# cuk.net
KiCad netlist of a schematic drawn in Altium Designer
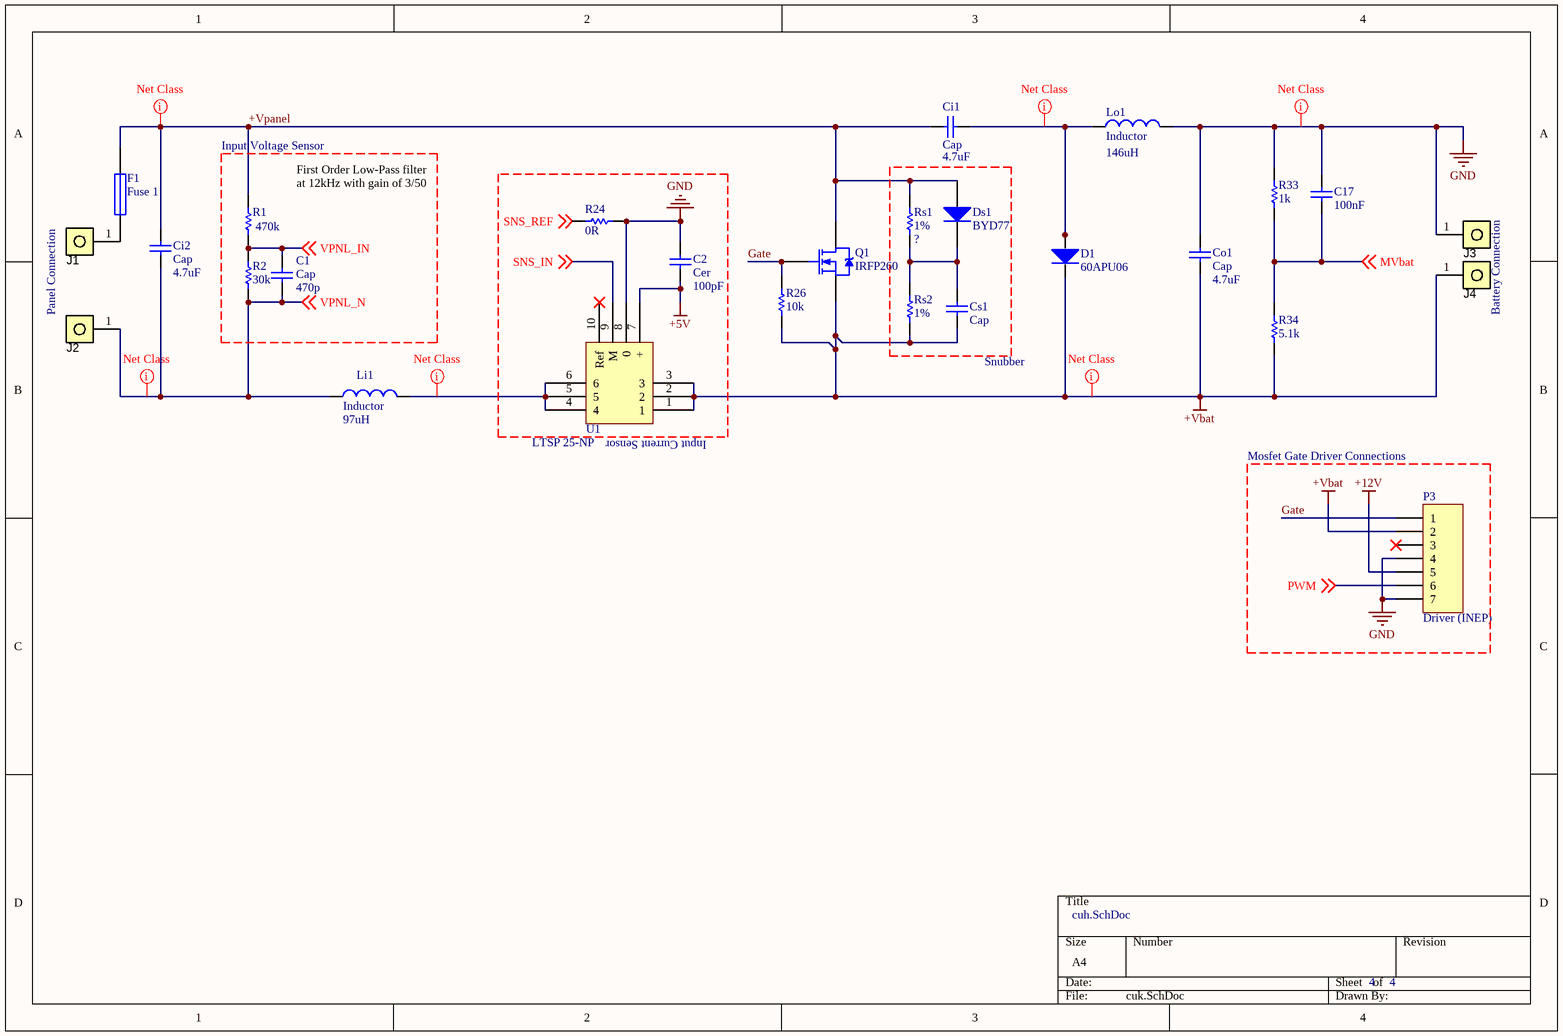
[diagram p0: cuk.SchDoc]

(export (version "E")
  (design (tool "Eeschema 10.0.6"))
  (components
    (comp (ref "C1")
      (value "Cap")
      (footprint "6-0805_N")
      (description "Capacitor")
      (fields (field (name "ALTIUM_VALUE") "470p") (field (name "PUBLISHER") "Altium Limited"))
      (libsource (lib "Miscellaneous Devices") (part "Cap"))
    )
    (comp (ref "C2")
      (value "Cer")
      (footprint "C1210_M")
      (description "Capacitor")
      (fields (field (name "ALTIUM_VALUE") "100pF") (field (name "PUBLISHER") "Altium Limited"))
      (libsource (lib "Miscellaneous Devices") (part "Cap"))
    )
    (comp (ref "C17")
      (value "100nF")
      (footprint "6-0805_M")
      (description "Capacitor")
      (fields (field (name "PUBLISHER") "Altium Limited"))
      (libsource (lib "ControladorCarga") (part "Cap_3"))
    )
    (comp (ref "Ci1")
      (value "Cap")
      (footprint "CAP4U7 EPCOS")
      (description "Capacitor")
      (fields (field (name "ALTIUM_VALUE") "4.7uF") (field (name "PUBLISHER") "Altium Limited"))
      (libsource (lib "Miscellaneous Devices") (part "Cap"))
    )
    (comp (ref "Ci2")
      (value "Cap")
      (footprint "CAP4U7 EPCOS")
      (description "Capacitor")
      (fields (field (name "ALTIUM_VALUE") "4.7uF") (field (name "PUBLISHER") "Altium Limited"))
      (libsource (lib "Miscellaneous Devices") (part "Cap"))
    )
    (comp (ref "Co1")
      (value "Cap")
      (footprint "CAP4U7 EPCOS")
      (description "Capacitor")
      (fields (field (name "ALTIUM_VALUE") "4.7uF") (field (name "PUBLISHER") "Altium Limited"))
      (libsource (lib "Miscellaneous Devices") (part "Cap"))
    )
    (comp (ref "Cs1")
      (value "Cap")
      (footprint "100nF")
      (description "Capacitor")
      (fields (field (name "PUBLISHER") "Altium Limited"))
      (libsource (lib "Miscellaneous Devices") (part "Cap"))
    )
    (comp (ref "D1")
      (value "60APU06")
      (footprint "to-247ac_horizontal")
      (libsource (lib "Prototipo") (part "60APU06"))
    )
    (comp (ref "Ds1")
      (value "BYD77")
      (footprint "SOD87")
      (description "1 Amp General Purpose Rectifier")
      (fields (field (name "PUBLISHER") "Altium Limited"))
      (libsource (lib "Miscellaneous Devices") (part "Diode 1N4002"))
    )
    (comp (ref "F1")
      (value "Fuse 1")
      (footprint "FUSE HOLDER 5X20")
      (description "Fuse")
      (fields (field (name "PUBLISHER") "Altium Limited"))
      (libsource (lib "TRACTEBEL") (part "Fuse 1"))
    )
    (comp (ref "J1") (value "~") (footprint "Parafuso") (libsource (lib "") (part "CONN_1_BIG_1")))
    (comp (ref "J2") (value "~") (footprint "Parafuso") (libsource (lib "") (part "CONN_1_BIG_1")))
    (comp (ref "J3")
      (value "~")
      (footprint "Parafuso")
      (libsource (lib "DatabaseAltium") (part "CONN_1_BIG"))
    )
    (comp (ref "J4")
      (value "~")
      (footprint "Parafuso")
      (libsource (lib "DatabaseAltium") (part "CONN_1_BIG"))
    )
    (comp (ref "Li1")
      (value "Inductor")
      (footprint "NEE-42-20-deitado")
      (fields (field (name "ALTIUM_VALUE") "97uH") (field (name "PUBLISHER") "Altium Limited"))
      (libsource (lib "Miscellaneous Devices") (part "Inductor"))
    )
    (comp (ref "Lo1")
      (value "Inductor")
      (footprint "NEE-42-20-deitado")
      (fields (field (name "ALTIUM_VALUE") "146uH") (field (name "PUBLISHER") "Altium Limited"))
      (libsource (lib "Miscellaneous Devices") (part "Inductor"))
    )
    (comp (ref "P3")
      (value "Driver (INEP)")
      (footprint "Driver INEP")
      (description "Header, 7-Pin")
      (fields (field (name "PUBLISHER") "Altium Limited"))
      (libsource (lib "Miscellaneous Connectors") (part "Header 7"))
    )
    (comp (ref "Q1")
      (value "IRFP260")
      (footprint "to-247ac_horizontal")
      (description "HEXFET Power MOSFET")
      (fields (field (name "PUBLISHER") "Altium Limited"))
      (libsource (lib "IR Discrete MOSFET - Power") (part "IRFP260"))
    )
    (comp (ref "R1")
      (value "470k")
      (footprint "6-0805_N")
      (description "Resistor")
      (fields (field (name "Comment") "Res1") (field (name "PUBLISHER") "Altium Limited"))
      (libsource (lib "Miscellaneous Devices") (part "Res1"))
    )
    (comp (ref "R2")
      (value "30k")
      (footprint "6-0805_N")
      (description "Resistor")
      (fields (field (name "Comment") "Res1") (field (name "PUBLISHER") "Altium Limited"))
      (libsource (lib "Miscellaneous Devices") (part "Res1"))
    )
    (comp (ref "R24")
      (value "0R")
      (footprint "6-0805_N")
      (description "Resistor")
      (fields (field (name "Comment") "Res1") (field (name "PUBLISHER") "Altium Limited"))
      (libsource (lib "Miscellaneous Devices") (part "Res1"))
    )
    (comp (ref "R26")
      (value "10k")
      (footprint "6-0805_N")
      (description "Resistor")
      (fields (field (name "Comment") "Res1") (field (name "PUBLISHER") "Altium Limited"))
      (libsource (lib "Miscellaneous Devices") (part "Res1"))
    )
    (comp (ref "R33")
      (value "1k")
      (footprint "6-0805_M")
      (description "Resistor")
      (fields (field (name "PUBLISHER") "Altium Limited"))
      (libsource (lib "ControladorCarga") (part "Res1"))
    )
    (comp (ref "R34")
      (value "5.1k")
      (footprint "6-0805_M")
      (description "Resistor")
      (fields (field (name "PUBLISHER") "Altium Limited"))
      (libsource (lib "ControladorCarga") (part "Res1"))
    )
    (comp (ref "Rs1")
      (value "1%")
      (footprint "AXIAL-0.3")
      (description "Resistor")
      (fields (field (name "ALTIUM_VALUE") "?") (field (name "PUBLISHER") "Altium Limited"))
      (libsource (lib "Miscellaneous Devices") (part "Res1"))
    )
    (comp (ref "Rs2")
      (value "1%")
      (footprint "AXIAL-0.3")
      (description "Resistor")
      (fields (field (name "PUBLISHER") "Altium Limited"))
      (libsource (lib "Miscellaneous Devices") (part "Res1"))
    )
    (comp (ref "U1")
      (value "LTSP 25-NP")
      (footprint "LTSP 25-NP")
      (description "Current Transducer LTSP (25 A)")
      (libsource (lib "LEM") (part "LTSP 25-NP"))
    )
  )
  (nets
    (net (code "1") (name "+5V") (class "Default")
      (node (ref "C2") (pin "1") (pinfunction "1_1") (pintype "passive"))
      (node (ref "U1") (pin "7") (pinfunction "+_7") (pintype "passive"))
    )
    (net (code "2") (name "+12V") (class "Default")
      (node (ref "P3") (pin "5") (pinfunction "5_5") (pintype "passive"))
    )
    (net (code "3") (name "+Vbat") (class "Default")
      (node (ref "Co1") (pin "1") (pinfunction "1_1") (pintype "passive"))
      (node (ref "Cs1") (pin "1") (pinfunction "1_1") (pintype "passive"))
      (node (ref "D1") (pin "2") (pinfunction "K_2") (pintype "passive"))
      (node (ref "J4") (pin "1") (pinfunction "1_1") (pintype "passive"))
      (node (ref "P3") (pin "2") (pinfunction "2_2") (pintype "passive"))
      (node (ref "Q1") (pin "3") (pinfunction "S_3") (pintype "passive"))
      (node (ref "R26") (pin "2") (pinfunction "2_2") (pintype "passive"))
      (node (ref "R34") (pin "1") (pinfunction "1_1") (pintype "passive"))
      (node (ref "Rs2") (pin "2") (pinfunction "2_2") (pintype "passive"))
      (node (ref "U1") (pin "1") (pinfunction "1_1") (pintype "passive"))
      (node (ref "U1") (pin "2") (pinfunction "2_2") (pintype "passive"))
      (node (ref "U1") (pin "3") (pinfunction "3_3") (pintype "passive"))
    )
    (net (code "4") (name "/+Vpanel") (class "Default")
      (node (ref "Ci1") (pin "1") (pinfunction "1_1") (pintype "passive"))
      (node (ref "Ci2") (pin "2") (pinfunction "2_2") (pintype "passive"))
      (node (ref "Ds1") (pin "1") (pinfunction "A_1") (pintype "passive"))
      (node (ref "F1") (pin "2") (pinfunction "2_2") (pintype "passive"))
      (node (ref "Q1") (pin "2") (pinfunction "D_2") (pintype "passive"))
      (node (ref "R1") (pin "1") (pinfunction "1_1") (pintype "passive"))
      (node (ref "Rs1") (pin "2") (pinfunction "2_2") (pintype "passive"))
    )
    (net (code "5") (name "/Gate") (class "Default")
      (node (ref "P3") (pin "1") (pinfunction "1_1") (pintype "passive"))
      (node (ref "Q1") (pin "1") (pinfunction "G_1") (pintype "passive"))
      (node (ref "R26") (pin "1") (pinfunction "1_1") (pintype "passive"))
    )
    (net (code "6") (name "GND") (class "Default")
      (node (ref "C17") (pin "2") (pinfunction "2_2") (pintype "passive"))
      (node (ref "C2") (pin "2") (pinfunction "2_2") (pintype "passive"))
      (node (ref "Co1") (pin "2") (pinfunction "2_2") (pintype "passive"))
      (node (ref "J3") (pin "1") (pinfunction "1_1") (pintype "passive"))
      (node (ref "Lo1") (pin "2") (pinfunction "2_2") (pintype "passive"))
      (node (ref "P3") (pin "4") (pinfunction "4_4") (pintype "passive"))
      (node (ref "P3") (pin "7") (pinfunction "7_7") (pintype "passive"))
      (node (ref "R24") (pin "2") (pinfunction "2_2") (pintype "passive"))
      (node (ref "R33") (pin "2") (pinfunction "2_2") (pintype "passive"))
      (node (ref "U1") (pin "8") (pinfunction "0_8") (pintype "passive"))
    )
    (net (code "7") (name "MVbat") (class "Default")
      (node (ref "C17") (pin "1") (pinfunction "1_1") (pintype "passive"))
      (node (ref "R33") (pin "1") (pinfunction "1_1") (pintype "passive"))
      (node (ref "R34") (pin "2") (pinfunction "2_2") (pintype "passive"))
    )
    (net (code "8") (name "Net-(Ci1-Pad2)") (class "Default")
      (node (ref "Ci1") (pin "2") (pinfunction "2_2") (pintype "passive"))
      (node (ref "D1") (pin "1") (pinfunction "A_1") (pintype "passive"))
      (node (ref "D1") (pin "3") (pinfunction "A_3") (pintype "passive"))
      (node (ref "Lo1") (pin "1") (pinfunction "1_1") (pintype "passive"))
    )
    (net (code "9") (name "Net-(Ds1-K)") (class "Default")
      (node (ref "Cs1") (pin "2") (pinfunction "2_2") (pintype "passive"))
      (node (ref "Ds1") (pin "2") (pinfunction "K_2") (pintype "passive"))
      (node (ref "Rs1") (pin "1") (pinfunction "1_1") (pintype "passive"))
      (node (ref "Rs2") (pin "1") (pinfunction "1_1") (pintype "passive"))
    )
    (net (code "10") (name "Net-(F1-Pad1)") (class "Default")
      (node (ref "F1") (pin "1") (pinfunction "1_1") (pintype "passive"))
      (node (ref "J1") (pin "1") (pinfunction "1_1") (pintype "passive"))
    )
    (net (code "11") (name "Net-(Li1-Pad2)") (class "Default")
      (node (ref "Li1") (pin "2") (pinfunction "2_2") (pintype "passive"))
      (node (ref "U1") (pin "4") (pinfunction "4_4") (pintype "passive"))
      (node (ref "U1") (pin "5") (pinfunction "5_5") (pintype "passive"))
      (node (ref "U1") (pin "6") (pinfunction "6_6") (pintype "passive"))
    )
    (net (code "12") (name "PWM") (class "Default")
      (node (ref "P3") (pin "6") (pinfunction "6_6") (pintype "passive"))
    )
    (net (code "13") (name "SNS_IN") (class "Default")
      (node (ref "U1") (pin "9") (pinfunction "M_9") (pintype "passive"))
    )
    (net (code "14") (name "SNS_REF") (class "Default")
      (node (ref "R24") (pin "1") (pinfunction "1_1") (pintype "passive"))
    )
    (net (code "15") (name "VPNL_IN") (class "Default")
      (node (ref "C1") (pin "1") (pinfunction "1_1") (pintype "passive"))
      (node (ref "R1") (pin "2") (pinfunction "2_2") (pintype "passive"))
      (node (ref "R2") (pin "1") (pinfunction "1_1") (pintype "passive"))
    )
    (net (code "16") (name "VPNL_N") (class "Default")
      (node (ref "C1") (pin "2") (pinfunction "2_2") (pintype "passive"))
      (node (ref "Ci2") (pin "1") (pinfunction "1_1") (pintype "passive"))
      (node (ref "J2") (pin "1") (pinfunction "1_1") (pintype "passive"))
      (node (ref "Li1") (pin "1") (pinfunction "1_1") (pintype "passive"))
      (node (ref "R2") (pin "2") (pinfunction "2_2") (pintype "passive"))
    )
    (net (code "17") (name "unconnected-(P3-Pad3)") (class "Default")
      (node (ref "P3") (pin "3") (pinfunction "3_3") (pintype "passive+no_connect"))
    )
    (net (code "18") (name "unconnected-(U1-Ref-Pad10)") (class "Default")
      (node (ref "U1") (pin "10") (pinfunction "Ref_10") (pintype "passive+no_connect"))
    )
  )
)
